# drutest2.net
KiCad netlist of a schematic drawn in EAGLE
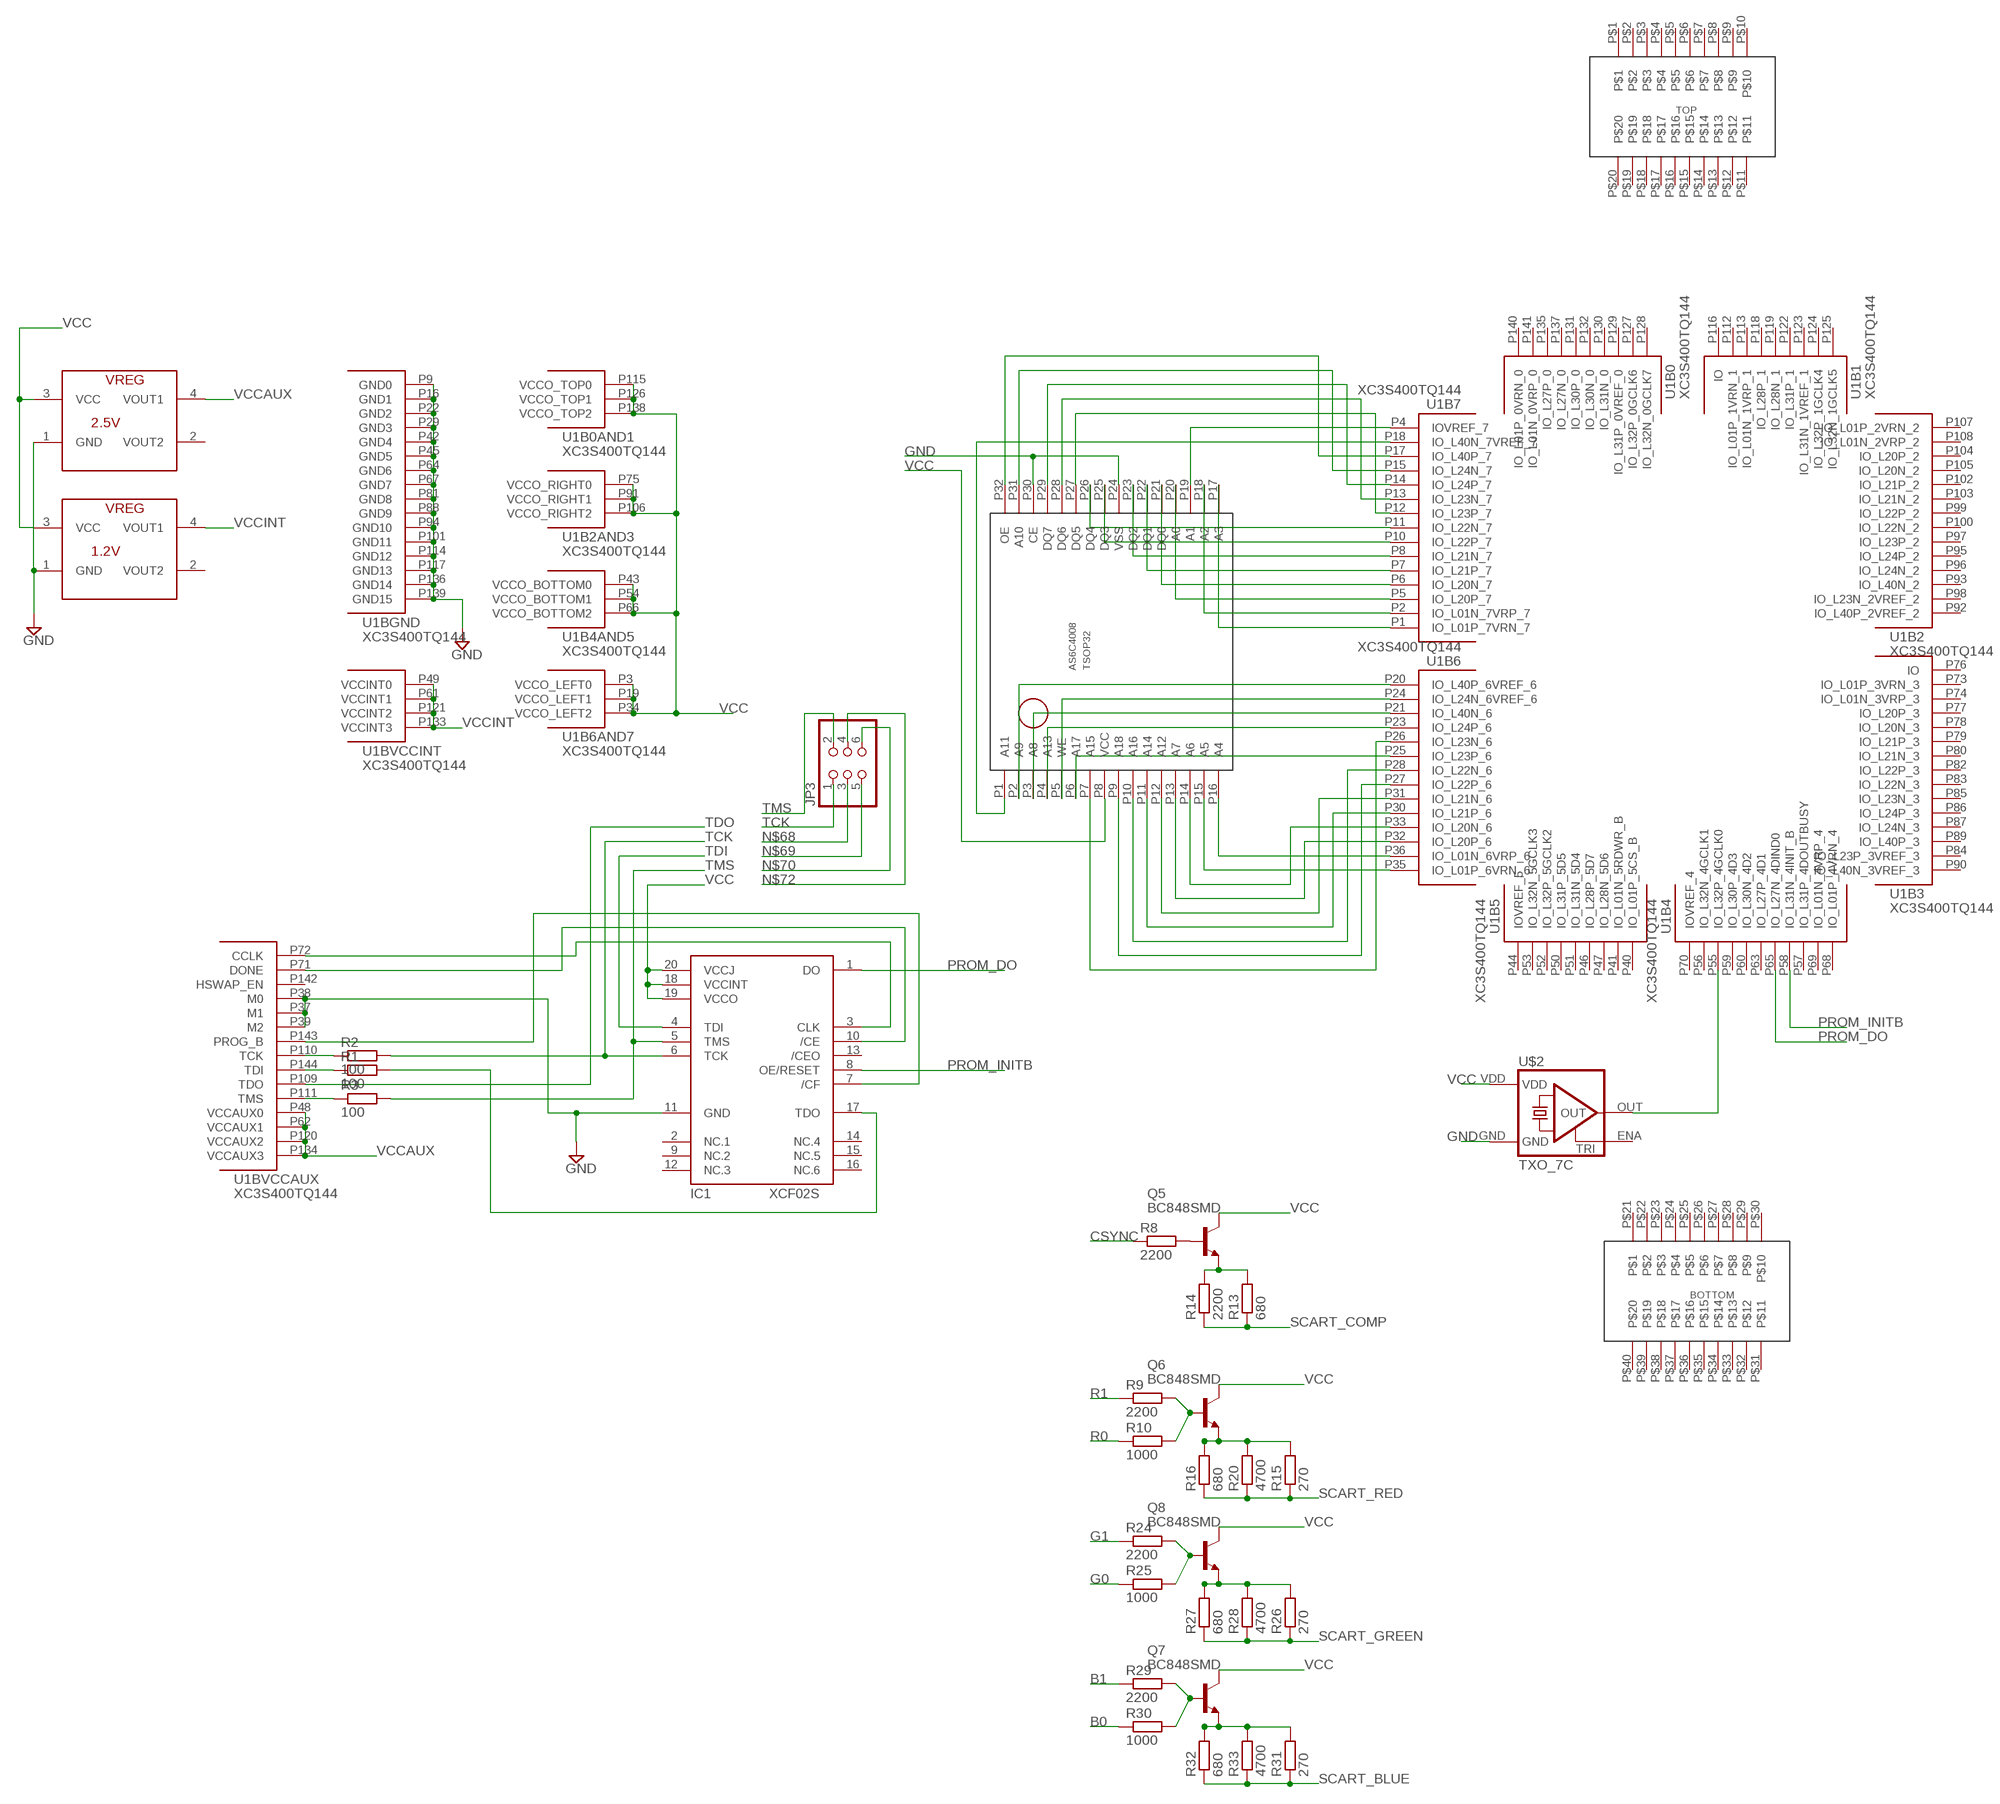
[diagram p0: schematic, sheet 1, part 1 of 2]
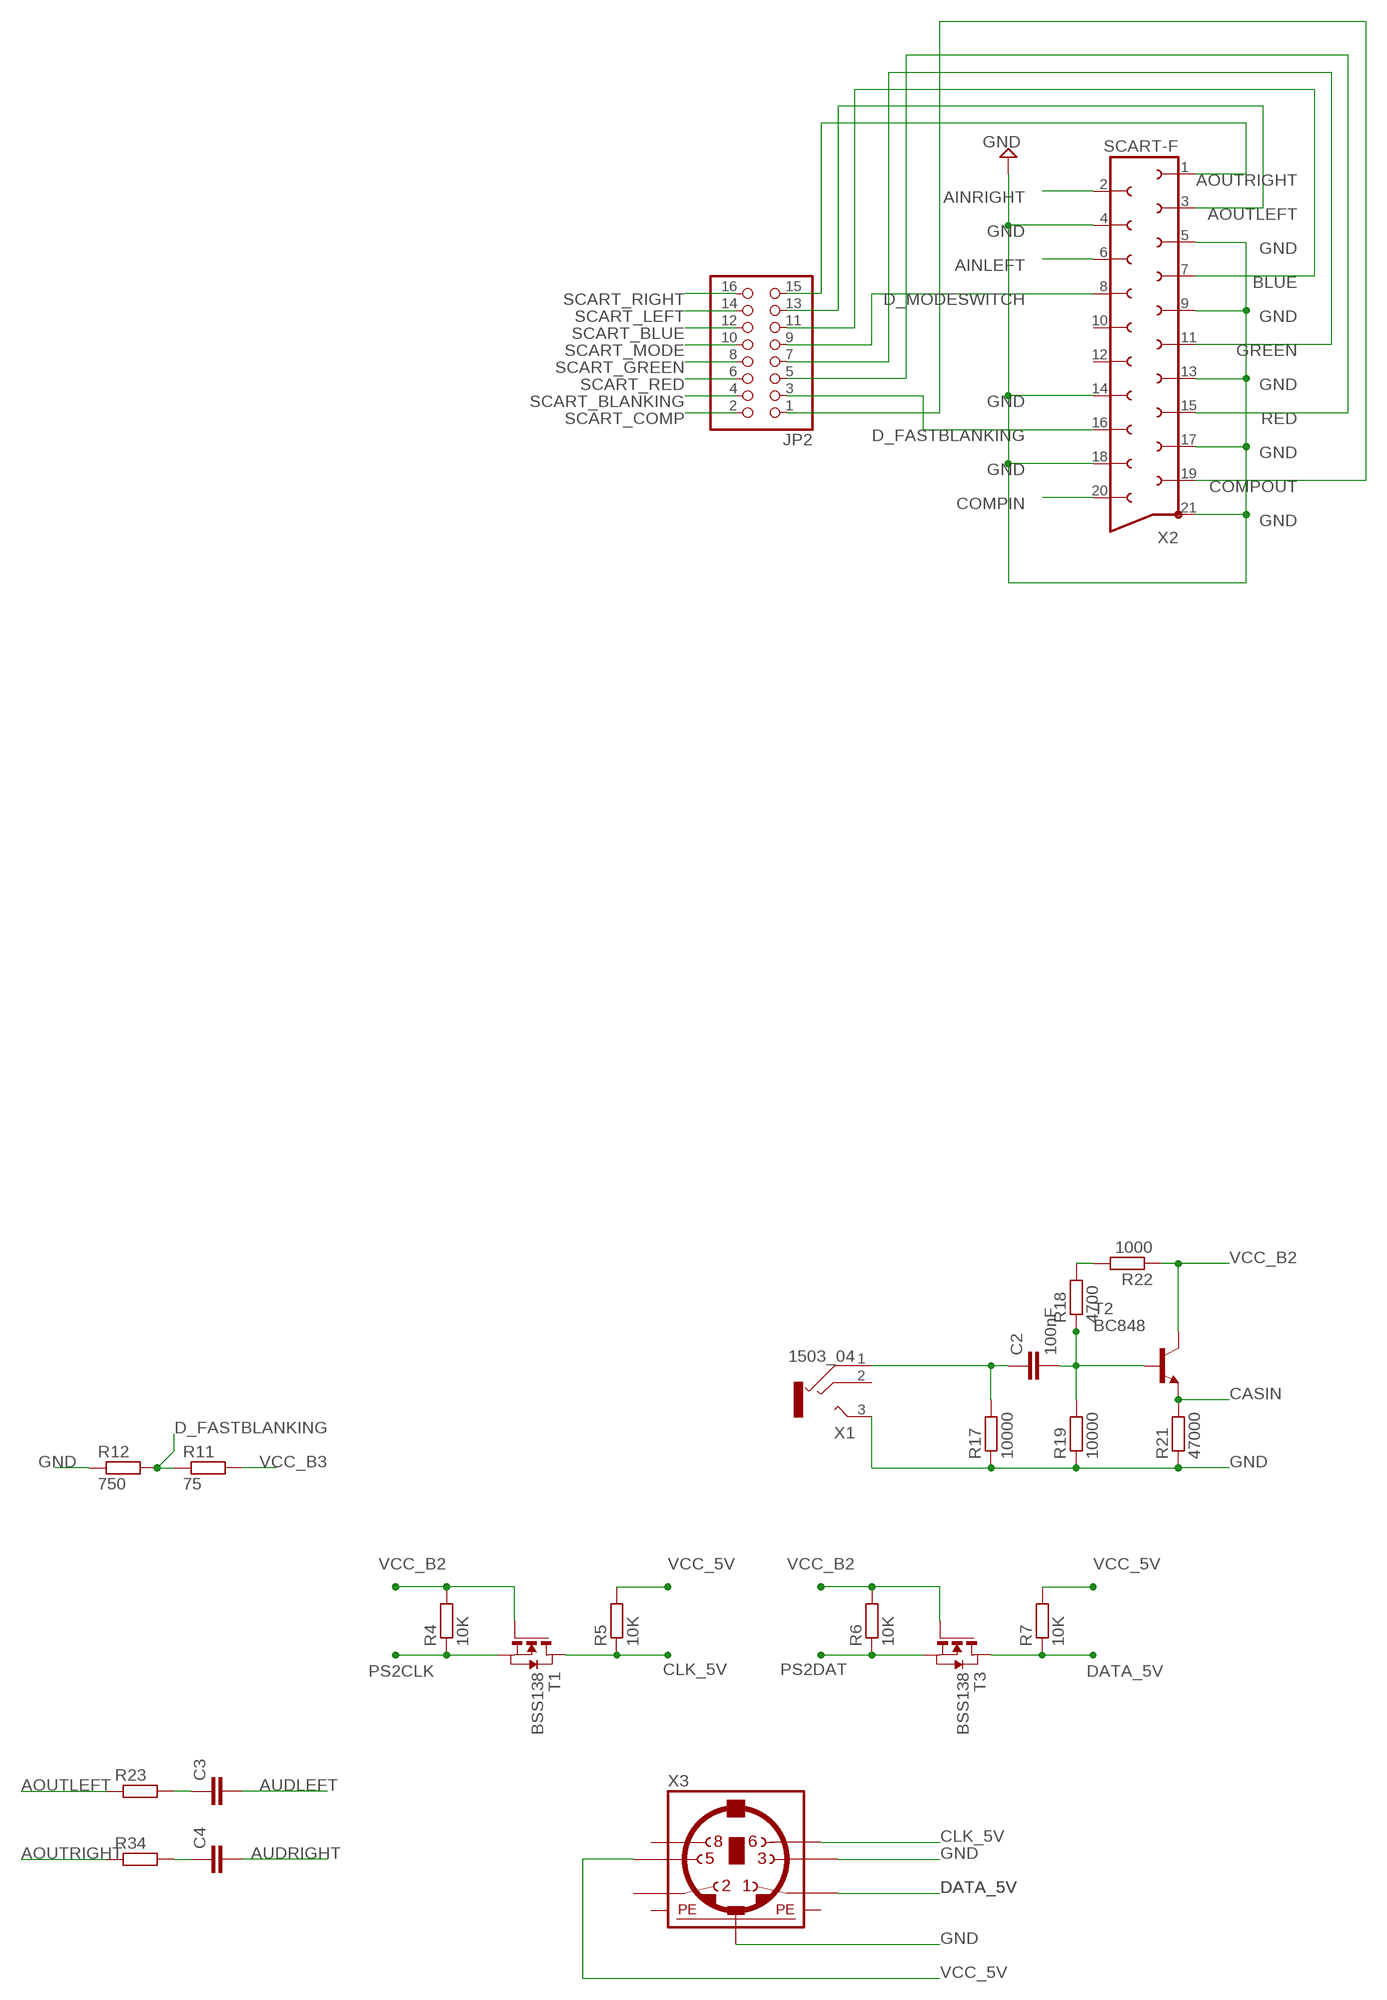
[diagram p1: schematic, sheet 1, part 2 of 2]

(export (version "E")
  (design (tool "Eeschema 10.0.6"))
  (components
    (comp (ref "C2")
      (value "100nF")
      (footprint "eagle-import:C0603")
      (libsource (lib "eagle-import") (part "C-EUC0603"))
    )
    (comp (ref "C3")
      (value "C-EUC0603")
      (footprint "eagle-import:C0603")
      (libsource (lib "eagle-import") (part "C-EUC0603"))
    )
    (comp (ref "C4")
      (value "C-EUC0603")
      (footprint "eagle-import:C0603")
      (libsource (lib "eagle-import") (part "C-EUC0603"))
    )
    (comp (ref "IC1")
      (value "XCF02S")
      (footprint "eagle-import:VO20")
      (libsource (lib "eagle-import") (part "XCF02S"))
    )
    (comp (ref "JP2")
      (value "PINHD-2X8")
      (footprint "eagle-import:2X08")
      (libsource (lib "eagle-import") (part "PINHD-2X8"))
    )
    (comp (ref "JP3")
      (value "PINHD-2X3")
      (footprint "eagle-import:2X03")
      (libsource (lib "eagle-import") (part "PINHD-2X3"))
    )
    (comp (ref "Q5")
      (value "BC848SMD")
      (footprint "eagle-import:SOT23")
      (libsource (lib "eagle-import") (part "BC848SMD"))
    )
    (comp (ref "Q6")
      (value "BC848SMD")
      (footprint "eagle-import:SOT23")
      (libsource (lib "eagle-import") (part "BC848SMD"))
    )
    (comp (ref "Q7")
      (value "BC848SMD")
      (footprint "eagle-import:SOT23")
      (libsource (lib "eagle-import") (part "BC848SMD"))
    )
    (comp (ref "Q8")
      (value "BC848SMD")
      (footprint "eagle-import:SOT23")
      (libsource (lib "eagle-import") (part "BC848SMD"))
    )
    (comp (ref "R1")
      (value "100")
      (footprint "eagle-import:R0805")
      (libsource (lib "eagle-import") (part "R-EU_R0805"))
    )
    (comp (ref "R2")
      (value "100")
      (footprint "eagle-import:R0805")
      (libsource (lib "eagle-import") (part "R-EU_R0805"))
    )
    (comp (ref "R3")
      (value "100")
      (footprint "eagle-import:R0805")
      (libsource (lib "eagle-import") (part "R-EU_R0805"))
    )
    (comp (ref "R4")
      (value "10K")
      (footprint "eagle-import:R0805")
      (libsource (lib "eagle-import") (part "R-EU_R0805"))
    )
    (comp (ref "R5")
      (value "10K")
      (footprint "eagle-import:R0805")
      (libsource (lib "eagle-import") (part "R-EU_R0805"))
    )
    (comp (ref "R6")
      (value "10K")
      (footprint "eagle-import:R0805")
      (libsource (lib "eagle-import") (part "R-EU_R0805"))
    )
    (comp (ref "R7")
      (value "10K")
      (footprint "eagle-import:R0805")
      (libsource (lib "eagle-import") (part "R-EU_R0805"))
    )
    (comp (ref "R8")
      (value "2200")
      (footprint "eagle-import:R0805")
      (libsource (lib "eagle-import") (part "R-EU_R0805"))
    )
    (comp (ref "R9")
      (value "2200")
      (footprint "eagle-import:R0805")
      (libsource (lib "eagle-import") (part "R-EU_R0805"))
    )
    (comp (ref "R10")
      (value "1000")
      (footprint "eagle-import:R0805")
      (libsource (lib "eagle-import") (part "R-EU_R0805"))
    )
    (comp (ref "R11")
      (value "75")
      (footprint "eagle-import:R0805")
      (libsource (lib "eagle-import") (part "R-EU_R0805"))
    )
    (comp (ref "R12")
      (value "750")
      (footprint "eagle-import:R0805")
      (libsource (lib "eagle-import") (part "R-EU_R0805"))
    )
    (comp (ref "R13")
      (value "680")
      (footprint "eagle-import:R0805")
      (libsource (lib "eagle-import") (part "R-EU_R0805"))
    )
    (comp (ref "R14")
      (value "2200")
      (footprint "eagle-import:R0805")
      (libsource (lib "eagle-import") (part "R-EU_R0805"))
    )
    (comp (ref "R15")
      (value "270")
      (footprint "eagle-import:R0805")
      (libsource (lib "eagle-import") (part "R-EU_R0805"))
    )
    (comp (ref "R16")
      (value "680")
      (footprint "eagle-import:R0805")
      (libsource (lib "eagle-import") (part "R-EU_R0805"))
    )
    (comp (ref "R17")
      (value "10000")
      (footprint "eagle-import:R0805")
      (libsource (lib "eagle-import") (part "R-EU_R0805"))
    )
    (comp (ref "R18")
      (value "4700")
      (footprint "eagle-import:R0805")
      (libsource (lib "eagle-import") (part "R-EU_R0805"))
    )
    (comp (ref "R19")
      (value "10000")
      (footprint "eagle-import:R0805")
      (libsource (lib "eagle-import") (part "R-EU_R0805"))
    )
    (comp (ref "R20")
      (value "4700")
      (footprint "eagle-import:R0805")
      (libsource (lib "eagle-import") (part "R-EU_R0805"))
    )
    (comp (ref "R21")
      (value "47000")
      (footprint "eagle-import:R0805")
      (libsource (lib "eagle-import") (part "R-EU_R0805"))
    )
    (comp (ref "R22")
      (value "1000")
      (footprint "eagle-import:R0805")
      (libsource (lib "eagle-import") (part "R-EU_R0805"))
    )
    (comp (ref "R23")
      (value "R-EU_M0805")
      (footprint "eagle-import:M0805")
      (libsource (lib "eagle-import") (part "resistor_R-EU_M0805"))
    )
    (comp (ref "R24")
      (value "2200")
      (footprint "eagle-import:R0805")
      (libsource (lib "eagle-import") (part "R-EU_R0805"))
    )
    (comp (ref "R25")
      (value "1000")
      (footprint "eagle-import:R0805")
      (libsource (lib "eagle-import") (part "R-EU_R0805"))
    )
    (comp (ref "R26")
      (value "270")
      (footprint "eagle-import:R0805")
      (libsource (lib "eagle-import") (part "R-EU_R0805"))
    )
    (comp (ref "R27")
      (value "680")
      (footprint "eagle-import:R0805")
      (libsource (lib "eagle-import") (part "R-EU_R0805"))
    )
    (comp (ref "R28")
      (value "4700")
      (footprint "eagle-import:R0805")
      (libsource (lib "eagle-import") (part "R-EU_R0805"))
    )
    (comp (ref "R29")
      (value "2200")
      (footprint "eagle-import:R0805")
      (libsource (lib "eagle-import") (part "R-EU_R0805"))
    )
    (comp (ref "R30")
      (value "1000")
      (footprint "eagle-import:R0805")
      (libsource (lib "eagle-import") (part "R-EU_R0805"))
    )
    (comp (ref "R31")
      (value "270")
      (footprint "eagle-import:R0805")
      (libsource (lib "eagle-import") (part "R-EU_R0805"))
    )
    (comp (ref "R32")
      (value "680")
      (footprint "eagle-import:R0805")
      (libsource (lib "eagle-import") (part "R-EU_R0805"))
    )
    (comp (ref "R33")
      (value "4700")
      (footprint "eagle-import:R0805")
      (libsource (lib "eagle-import") (part "R-EU_R0805"))
    )
    (comp (ref "R34")
      (value "R-EU_M0805")
      (footprint "eagle-import:M0805")
      (libsource (lib "eagle-import") (part "resistor_R-EU_M0805"))
    )
    (comp (ref "T1")
      (value "BSS138")
      (footprint "eagle-import:SOT-23")
      (libsource (lib "eagle-import") (part "NMOSSOT23"))
    )
    (comp (ref "T2")
      (value "BC848")
      (footprint "eagle-import:SOT23")
      (libsource (lib "eagle-import") (part "BC848"))
    )
    (comp (ref "T3")
      (value "BSS138")
      (footprint "eagle-import:SOT-23")
      (libsource (lib "eagle-import") (part "NMOSSOT23"))
    )
    (comp (ref "U$1")
      (value "AS6C4008")
      (footprint "eagle-import:TSOP32")
      (libsource (lib "eagle-import") (part "AS6C4008"))
    )
    (comp (ref "U$2")
      (value "TXO_7C")
      (footprint "eagle-import:OSC_7C")
      (libsource (lib "eagle-import") (part "TXO_7C"))
    )
    (comp (ref "U$3")
      (value "2.5V")
      (footprint "eagle-import:SOT223")
      (libsource (lib "eagle-import") (part "NX1117"))
    )
    (comp (ref "U$4")
      (value "1.2V")
      (footprint "eagle-import:SOT223")
      (libsource (lib "eagle-import") (part "NX1117"))
    )
    (comp (ref "U$5")
      (value "EXPHDR")
      (footprint "eagle-import:EXPHDR")
      (libsource (lib "eagle-import") (part "EXPHDR"))
    )
    (comp (ref "U1")
      (value "XC3S400TQ144")
      (footprint "eagle-import:TQ144")
      (libsource (lib "eagle-import") (part "XC3S400TQ144"))
    )
    (comp (ref "X1")
      (value "1503_04")
      (footprint "eagle-import:1503_04")
      (libsource (lib "eagle-import") (part "1503_04"))
    )
    (comp (ref "X2")
      (value "SCART-F")
      (footprint "eagle-import:SCART-F")
      (libsource (lib "eagle-import") (part "SCART-F"))
    )
    (comp (ref "X3")
      (value "MINI_DIN_6")
      (footprint "eagle-import:M_DIN6")
      (libsource (lib "eagle-import") (part "MINI_DIN_6"))
    )
  )
  (nets
    (net (code "1") (name "/AINLEFT") (class "Default")
      (node (ref "X2") (pin "6") (pinfunction "6_6") (pintype "passive"))
    )
    (net (code "2") (name "/AINRIGHT") (class "Default")
      (node (ref "X2") (pin "2") (pinfunction "2_2") (pintype "passive"))
    )
    (net (code "3") (name "/AOUTLEFT") (class "Default")
      (node (ref "JP2") (pin "13") (pinfunction "13_13") (pintype "passive"))
      (node (ref "R23") (pin "1") (pinfunction "1_1") (pintype "passive"))
      (node (ref "X2") (pin "3") (pinfunction "3_3") (pintype "passive"))
    )
    (net (code "4") (name "/AOUTRIGHT") (class "Default")
      (node (ref "JP2") (pin "15") (pinfunction "15_15") (pintype "passive"))
      (node (ref "R34") (pin "1") (pinfunction "1_1") (pintype "passive"))
      (node (ref "X2") (pin "1") (pinfunction "1_1") (pintype "passive"))
    )
    (net (code "5") (name "/AUDLEFT") (class "Default")
      (node (ref "C3") (pin "2") (pinfunction "2_2") (pintype "passive"))
    )
    (net (code "6") (name "/AUDRIGHT") (class "Default")
      (node (ref "C4") (pin "2") (pinfunction "2_2") (pintype "passive"))
    )
    (net (code "7") (name "/B0") (class "Default")
      (node (ref "R30") (pin "1") (pinfunction "1_1") (pintype "passive"))
    )
    (net (code "8") (name "/B1") (class "Default")
      (node (ref "R29") (pin "1") (pinfunction "1_1") (pintype "passive"))
    )
    (net (code "9") (name "/BLUE") (class "Default")
      (node (ref "JP2") (pin "11") (pinfunction "11_11") (pintype "passive"))
      (node (ref "X2") (pin "7") (pinfunction "7_7") (pintype "passive"))
    )
    (net (code "10") (name "/CASIN") (class "Default")
      (node (ref "R21") (pin "2") (pinfunction "2_2") (pintype "passive"))
      (node (ref "T2") (pin "2") (pinfunction "E_2") (pintype "passive"))
    )
    (net (code "11") (name "/CLK_5V") (class "Default")
      (node (ref "R5") (pin "1") (pinfunction "1_1") (pintype "passive"))
      (node (ref "T1") (pin "1") (pinfunction "D_1") (pintype "passive"))
      (node (ref "X3") (pin "6") (pinfunction "6_6") (pintype "passive"))
    )
    (net (code "12") (name "/COMPIN") (class "Default")
      (node (ref "X2") (pin "20") (pinfunction "20_20") (pintype "passive"))
    )
    (net (code "13") (name "/COMPOUT") (class "Default")
      (node (ref "JP2") (pin "1") (pinfunction "1_1") (pintype "passive"))
      (node (ref "X2") (pin "19") (pinfunction "19_19") (pintype "passive"))
    )
    (net (code "14") (name "/CSYNC") (class "Default")
      (node (ref "R8") (pin "1") (pinfunction "1_1") (pintype "passive"))
    )
    (net (code "15") (name "/DATA_5V") (class "Default")
      (node (ref "R7") (pin "1") (pinfunction "1_1") (pintype "passive"))
      (node (ref "T3") (pin "1") (pinfunction "D_1") (pintype "passive"))
      (node (ref "X3") (pin "1") (pinfunction "1_1") (pintype "passive"))
    )
    (net (code "16") (name "/D_FASTBLANKING") (class "Default")
      (node (ref "JP2") (pin "3") (pinfunction "3_3") (pintype "passive"))
      (node (ref "R11") (pin "1") (pinfunction "1_1") (pintype "passive"))
      (node (ref "R12") (pin "2") (pinfunction "2_2") (pintype "passive"))
      (node (ref "X2") (pin "16") (pinfunction "16_16") (pintype "passive"))
    )
    (net (code "17") (name "/D_MODESWITCH") (class "Default")
      (node (ref "JP2") (pin "9") (pinfunction "9_9") (pintype "passive"))
      (node (ref "X2") (pin "8") (pinfunction "8_8") (pintype "passive"))
    )
    (net (code "18") (name "/G0") (class "Default")
      (node (ref "R25") (pin "1") (pinfunction "1_1") (pintype "passive"))
    )
    (net (code "19") (name "/G1") (class "Default")
      (node (ref "R24") (pin "1") (pinfunction "1_1") (pintype "passive"))
    )
    (net (code "20") (name "/GREEN") (class "Default")
      (node (ref "JP2") (pin "7") (pinfunction "7_7") (pintype "passive"))
      (node (ref "X2") (pin "11") (pinfunction "11_11") (pintype "passive"))
    )
    (net (code "21") (name "/N$68") (class "Default")
      (node (ref "JP3") (pin "3") (pinfunction "3_3") (pintype "passive"))
    )
    (net (code "22") (name "/N$69") (class "Default")
      (node (ref "JP3") (pin "5") (pinfunction "5_5") (pintype "passive"))
    )
    (net (code "23") (name "/N$70") (class "Default")
      (node (ref "JP3") (pin "6") (pinfunction "6_6") (pintype "passive"))
    )
    (net (code "24") (name "/N$72") (class "Default")
      (node (ref "JP3") (pin "4") (pinfunction "4_4") (pintype "passive"))
    )
    (net (code "25") (name "/PE1") (class "Default")
      (node (ref "X3") (pin "SH1") (pinfunction "PE1_SH1") (pintype "power_in"))
    )
    (net (code "26") (name "/PE3") (class "Default")
      (node (ref "X3") (pin "SH3") (pinfunction "PE3_SH3") (pintype "power_in"))
    )
    (net (code "27") (name "/PROM_DO") (class "Default")
      (node (ref "IC1") (pin "1") (pinfunction "DO_1") (pintype "bidirectional"))
      (node (ref "U1") (pin "P65") (pinfunction "IO_L27N_4DIND0_P65") (pintype "bidirectional"))
    )
    (net (code "28") (name "/PROM_INITB") (class "Default")
      (node (ref "IC1") (pin "8") (pinfunction "OE/RESET_8") (pintype "bidirectional"))
      (node (ref "U1") (pin "P58") (pinfunction "IO_L31N_4INIT_B_P58") (pintype "bidirectional"))
    )
    (net (code "29") (name "/PS2CLK") (class "Default")
      (node (ref "R4") (pin "1") (pinfunction "1_1") (pintype "passive"))
      (node (ref "T1") (pin "2") (pinfunction "S_2") (pintype "passive"))
    )
    (net (code "30") (name "/PS2DAT") (class "Default")
      (node (ref "R6") (pin "1") (pinfunction "1_1") (pintype "passive"))
      (node (ref "T3") (pin "2") (pinfunction "S_2") (pintype "passive"))
    )
    (net (code "31") (name "/R0") (class "Default")
      (node (ref "R10") (pin "1") (pinfunction "1_1") (pintype "passive"))
    )
    (net (code "32") (name "/R1") (class "Default")
      (node (ref "R9") (pin "1") (pinfunction "1_1") (pintype "passive"))
    )
    (net (code "33") (name "/RED") (class "Default")
      (node (ref "JP2") (pin "5") (pinfunction "5_5") (pintype "passive"))
      (node (ref "X2") (pin "15") (pinfunction "15_15") (pintype "passive"))
    )
    (net (code "34") (name "/SCART_BLANKING") (class "Default")
      (node (ref "JP2") (pin "4") (pinfunction "4_4") (pintype "passive"))
    )
    (net (code "35") (name "/SCART_BLUE") (class "Default")
      (node (ref "JP2") (pin "12") (pinfunction "12_12") (pintype "passive"))
      (node (ref "R31") (pin "1") (pinfunction "1_1") (pintype "passive"))
      (node (ref "R32") (pin "1") (pinfunction "1_1") (pintype "passive"))
      (node (ref "R33") (pin "1") (pinfunction "1_1") (pintype "passive"))
    )
    (net (code "36") (name "/SCART_COMP") (class "Default")
      (node (ref "JP2") (pin "2") (pinfunction "2_2") (pintype "passive"))
      (node (ref "R13") (pin "1") (pinfunction "1_1") (pintype "passive"))
      (node (ref "R14") (pin "1") (pinfunction "1_1") (pintype "passive"))
    )
    (net (code "37") (name "/SCART_GREEN") (class "Default")
      (node (ref "JP2") (pin "8") (pinfunction "8_8") (pintype "passive"))
      (node (ref "R26") (pin "1") (pinfunction "1_1") (pintype "passive"))
      (node (ref "R27") (pin "1") (pinfunction "1_1") (pintype "passive"))
      (node (ref "R28") (pin "1") (pinfunction "1_1") (pintype "passive"))
    )
    (net (code "38") (name "/SCART_LEFT") (class "Default")
      (node (ref "JP2") (pin "14") (pinfunction "14_14") (pintype "passive"))
    )
    (net (code "39") (name "/SCART_MODE") (class "Default")
      (node (ref "JP2") (pin "10") (pinfunction "10_10") (pintype "passive"))
    )
    (net (code "40") (name "/SCART_RED") (class "Default")
      (node (ref "JP2") (pin "6") (pinfunction "6_6") (pintype "passive"))
      (node (ref "R15") (pin "1") (pinfunction "1_1") (pintype "passive"))
      (node (ref "R16") (pin "1") (pinfunction "1_1") (pintype "passive"))
      (node (ref "R20") (pin "1") (pinfunction "1_1") (pintype "passive"))
    )
    (net (code "41") (name "/SCART_RIGHT") (class "Default")
      (node (ref "JP2") (pin "16") (pinfunction "16_16") (pintype "passive"))
    )
    (net (code "42") (name "/TCK") (class "Default")
      (node (ref "IC1") (pin "6") (pinfunction "TCK_6") (pintype "bidirectional"))
      (node (ref "JP3") (pin "1") (pinfunction "1_1") (pintype "passive"))
      (node (ref "R2") (pin "2") (pinfunction "2_2") (pintype "passive"))
    )
    (net (code "43") (name "/TDI") (class "Default")
      (node (ref "IC1") (pin "4") (pinfunction "TDI_4") (pintype "bidirectional"))
    )
    (net (code "44") (name "/TDO") (class "Default")
      (node (ref "U1") (pin "P109") (pinfunction "TDO_P109") (pintype "bidirectional"))
    )
    (net (code "45") (name "/TMS") (class "Default")
      (node (ref "IC1") (pin "5") (pinfunction "TMS_5") (pintype "bidirectional"))
      (node (ref "JP3") (pin "2") (pinfunction "2_2") (pintype "passive"))
      (node (ref "R3") (pin "2") (pinfunction "2_2") (pintype "passive"))
    )
    (net (code "46") (name "/VCC") (class "Default")
      (node (ref "IC1") (pin "18") (pinfunction "VCCINT_18") (pintype "bidirectional"))
      (node (ref "IC1") (pin "19") (pinfunction "VCCO_19") (pintype "bidirectional"))
      (node (ref "IC1") (pin "20") (pinfunction "VCCJ_20") (pintype "bidirectional"))
      (node (ref "Q5") (pin "3") (pinfunction "C_3") (pintype "passive"))
      (node (ref "Q6") (pin "3") (pinfunction "C_3") (pintype "passive"))
      (node (ref "Q7") (pin "3") (pinfunction "C_3") (pintype "passive"))
      (node (ref "Q8") (pin "3") (pinfunction "C_3") (pintype "passive"))
      (node (ref "U$1") (pin "P8") (pinfunction "VCC_P8") (pintype "bidirectional"))
      (node (ref "U$2") (pin "VDD") (pinfunction "VDD_VDD") (pintype "power_in"))
      (node (ref "U$3") (pin "3") (pinfunction "VCC_3") (pintype "bidirectional"))
      (node (ref "U$4") (pin "3") (pinfunction "VCC_3") (pintype "bidirectional"))
      (node (ref "U1") (pin "P106") (pinfunction "VCCO_RIGHT2_P106") (pintype "passive"))
      (node (ref "U1") (pin "P115") (pinfunction "VCCO_TOP0_P115") (pintype "passive"))
      (node (ref "U1") (pin "P126") (pinfunction "VCCO_TOP1_P126") (pintype "passive"))
      (node (ref "U1") (pin "P138") (pinfunction "VCCO_TOP2_P138") (pintype "passive"))
      (node (ref "U1") (pin "P19") (pinfunction "VCCO_LEFT1_P19") (pintype "passive"))
      (node (ref "U1") (pin "P3") (pinfunction "VCCO_LEFT0_P3") (pintype "passive"))
      (node (ref "U1") (pin "P34") (pinfunction "VCCO_LEFT2_P34") (pintype "passive"))
      (node (ref "U1") (pin "P43") (pinfunction "VCCO_BOTTOM0_P43") (pintype "passive"))
      (node (ref "U1") (pin "P54") (pinfunction "VCCO_BOTTOM1_P54") (pintype "passive"))
      (node (ref "U1") (pin "P66") (pinfunction "VCCO_BOTTOM2_P66") (pintype "passive"))
      (node (ref "U1") (pin "P75") (pinfunction "VCCO_RIGHT0_P75") (pintype "passive"))
      (node (ref "U1") (pin "P91") (pinfunction "VCCO_RIGHT1_P91") (pintype "passive"))
    )
    (net (code "47") (name "/VCCAUX") (class "Default")
      (node (ref "U$3") (pin "4") (pinfunction "VOUT1_4") (pintype "bidirectional"))
      (node (ref "U1") (pin "P120") (pinfunction "VCCAUX2_P120") (pintype "passive"))
      (node (ref "U1") (pin "P134") (pinfunction "VCCAUX3_P134") (pintype "passive"))
      (node (ref "U1") (pin "P48") (pinfunction "VCCAUX0_P48") (pintype "passive"))
      (node (ref "U1") (pin "P62") (pinfunction "VCCAUX1_P62") (pintype "passive"))
    )
    (net (code "48") (name "/VCCINT") (class "Default")
      (node (ref "U$4") (pin "4") (pinfunction "VOUT1_4") (pintype "bidirectional"))
      (node (ref "U1") (pin "P121") (pinfunction "VCCINT2_P121") (pintype "passive"))
      (node (ref "U1") (pin "P133") (pinfunction "VCCINT3_P133") (pintype "passive"))
      (node (ref "U1") (pin "P49") (pinfunction "VCCINT0_P49") (pintype "passive"))
      (node (ref "U1") (pin "P61") (pinfunction "VCCINT1_P61") (pintype "passive"))
    )
    (net (code "49") (name "/VCC_5V") (class "Default")
      (node (ref "R5") (pin "2") (pinfunction "2_2") (pintype "passive"))
      (node (ref "R7") (pin "2") (pinfunction "2_2") (pintype "passive"))
      (node (ref "X3") (pin "5") (pinfunction "5_5") (pintype "passive"))
    )
    (net (code "50") (name "/VCC_B2") (class "Default")
      (node (ref "R22") (pin "1") (pinfunction "1_1") (pintype "passive"))
      (node (ref "R4") (pin "2") (pinfunction "2_2") (pintype "passive"))
      (node (ref "R6") (pin "2") (pinfunction "2_2") (pintype "passive"))
      (node (ref "T1") (pin "3") (pinfunction "G_3") (pintype "passive"))
      (node (ref "T2") (pin "3") (pinfunction "C_3") (pintype "passive"))
      (node (ref "T3") (pin "3") (pinfunction "G_3") (pintype "passive"))
    )
    (net (code "51") (name "/VCC_B3") (class "Default")
      (node (ref "R11") (pin "2") (pinfunction "2_2") (pintype "passive"))
    )
    (net (code "52") (name "GND") (class "Default")
      (node (ref "IC1") (pin "11") (pinfunction "GND_11") (pintype "bidirectional"))
      (node (ref "R12") (pin "1") (pinfunction "1_1") (pintype "passive"))
      (node (ref "R17") (pin "1") (pinfunction "1_1") (pintype "passive"))
      (node (ref "R19") (pin "1") (pinfunction "1_1") (pintype "passive"))
      (node (ref "R21") (pin "1") (pinfunction "1_1") (pintype "passive"))
      (node (ref "U$1") (pin "P24") (pinfunction "VSS_P24") (pintype "bidirectional"))
      (node (ref "U$1") (pin "P30") (pinfunction "CE_P30") (pintype "bidirectional"))
      (node (ref "U$2") (pin "GND") (pinfunction "GND_GND") (pintype "power_in"))
      (node (ref "U$3") (pin "1") (pinfunction "GND_1") (pintype "bidirectional"))
      (node (ref "U$4") (pin "1") (pinfunction "GND_1") (pintype "bidirectional"))
      (node (ref "U1") (pin "P101") (pinfunction "GND11_P101") (pintype "passive"))
      (node (ref "U1") (pin "P114") (pinfunction "GND12_P114") (pintype "passive"))
      (node (ref "U1") (pin "P117") (pinfunction "GND13_P117") (pintype "passive"))
      (node (ref "U1") (pin "P136") (pinfunction "GND14_P136") (pintype "passive"))
      (node (ref "U1") (pin "P139") (pinfunction "GND15_P139") (pintype "passive"))
      (node (ref "U1") (pin "P16") (pinfunction "GND1_P16") (pintype "passive"))
      (node (ref "U1") (pin "P22") (pinfunction "GND2_P22") (pintype "passive"))
      (node (ref "U1") (pin "P29") (pinfunction "GND3_P29") (pintype "passive"))
      (node (ref "U1") (pin "P37") (pinfunction "M1_P37") (pintype "bidirectional"))
      (node (ref "U1") (pin "P38") (pinfunction "M0_P38") (pintype "bidirectional"))
      (node (ref "U1") (pin "P39") (pinfunction "M2_P39") (pintype "bidirectional"))
      (node (ref "U1") (pin "P42") (pinfunction "GND4_P42") (pintype "passive"))
      (node (ref "U1") (pin "P45") (pinfunction "GND5_P45") (pintype "passive"))
      (node (ref "U1") (pin "P64") (pinfunction "GND6_P64") (pintype "passive"))
      (node (ref "U1") (pin "P67") (pinfunction "GND7_P67") (pintype "passive"))
      (node (ref "U1") (pin "P81") (pinfunction "GND8_P81") (pintype "passive"))
      (node (ref "U1") (pin "P88") (pinfunction "GND9_P88") (pintype "passive"))
      (node (ref "U1") (pin "P9") (pinfunction "GND0_P9") (pintype "passive"))
      (node (ref "U1") (pin "P94") (pinfunction "GND10_P94") (pintype "passive"))
      (node (ref "X1") (pin "3") (pinfunction "2_3") (pintype "passive"))
      (node (ref "X2") (pin "13") (pinfunction "13_13") (pintype "passive"))
      (node (ref "X2") (pin "14") (pinfunction "14_14") (pintype "passive"))
      (node (ref "X2") (pin "17") (pinfunction "17_17") (pintype "passive"))
      (node (ref "X2") (pin "18") (pinfunction "18_18") (pintype "passive"))
      (node (ref "X2") (pin "21") (pinfunction "21_21") (pintype "passive"))
      (node (ref "X2") (pin "4") (pinfunction "4_4") (pintype "passive"))
      (node (ref "X2") (pin "5") (pinfunction "5_5") (pintype "passive"))
      (node (ref "X2") (pin "9") (pinfunction "9_9") (pintype "passive"))
      (node (ref "X3") (pin "3") (pinfunction "3_3") (pintype "passive"))
      (node (ref "X3") (pin "SH2") (pinfunction "PE2_SH2") (pintype "power_in"))
    )
    (net (code "53") (name "Net-(C2-Pad1)") (class "Default")
      (node (ref "C2") (pin "1") (pinfunction "1_1") (pintype "passive"))
      (node (ref "R17") (pin "2") (pinfunction "2_2") (pintype "passive"))
      (node (ref "X1") (pin "1") (pinfunction "1_1") (pintype "passive"))
    )
    (net (code "54") (name "Net-(C3-Pad1)") (class "Default")
      (node (ref "C3") (pin "1") (pinfunction "1_1") (pintype "passive"))
      (node (ref "R23") (pin "2") (pinfunction "2_2") (pintype "passive"))
    )
    (net (code "55") (name "Net-(C4-Pad1)") (class "Default")
      (node (ref "C4") (pin "1") (pinfunction "1_1") (pintype "passive"))
      (node (ref "R34") (pin "2") (pinfunction "2_2") (pintype "passive"))
    )
    (net (code "56") (name "Net-(IC1-CLK)") (class "Default")
      (node (ref "IC1") (pin "3") (pinfunction "CLK_3") (pintype "bidirectional"))
      (node (ref "U1") (pin "P72") (pinfunction "CCLK_P72") (pintype "bidirectional"))
    )
    (net (code "57") (name "Net-(IC1-TDO)") (class "Default")
      (node (ref "IC1") (pin "17") (pinfunction "TDO_17") (pintype "bidirectional"))
      (node (ref "R1") (pin "2") (pinfunction "2_2") (pintype "passive"))
    )
    (net (code "58") (name "Net-(IC1-{slash}CE)") (class "Default")
      (node (ref "IC1") (pin "10") (pinfunction "/CE_10") (pintype "bidirectional"))
      (node (ref "U1") (pin "P71") (pinfunction "DONE_P71") (pintype "bidirectional"))
    )
    (net (code "59") (name "Net-(IC1-{slash}CF)") (class "Default")
      (node (ref "IC1") (pin "7") (pinfunction "/CF_7") (pintype "bidirectional"))
      (node (ref "U1") (pin "P143") (pinfunction "PROG_B_P143") (pintype "bidirectional"))
    )
    (net (code "60") (name "Net-(Q5-B)") (class "Default")
      (node (ref "Q5") (pin "1") (pinfunction "B_1") (pintype "passive"))
      (node (ref "R8") (pin "2") (pinfunction "2_2") (pintype "passive"))
    )
    (net (code "61") (name "Net-(Q5-E)") (class "Default")
      (node (ref "Q5") (pin "2") (pinfunction "E_2") (pintype "passive"))
      (node (ref "R13") (pin "2") (pinfunction "2_2") (pintype "passive"))
      (node (ref "R14") (pin "2") (pinfunction "2_2") (pintype "passive"))
    )
    (net (code "62") (name "Net-(Q6-B)") (class "Default")
      (node (ref "Q6") (pin "1") (pinfunction "B_1") (pintype "passive"))
      (node (ref "R10") (pin "2") (pinfunction "2_2") (pintype "passive"))
      (node (ref "R9") (pin "2") (pinfunction "2_2") (pintype "passive"))
    )
    (net (code "63") (name "Net-(Q6-E)") (class "Default")
      (node (ref "Q6") (pin "2") (pinfunction "E_2") (pintype "passive"))
      (node (ref "R15") (pin "2") (pinfunction "2_2") (pintype "passive"))
      (node (ref "R16") (pin "2") (pinfunction "2_2") (pintype "passive"))
      (node (ref "R20") (pin "2") (pinfunction "2_2") (pintype "passive"))
    )
    (net (code "64") (name "Net-(Q7-B)") (class "Default")
      (node (ref "Q7") (pin "1") (pinfunction "B_1") (pintype "passive"))
      (node (ref "R29") (pin "2") (pinfunction "2_2") (pintype "passive"))
      (node (ref "R30") (pin "2") (pinfunction "2_2") (pintype "passive"))
    )
    (net (code "65") (name "Net-(Q7-E)") (class "Default")
      (node (ref "Q7") (pin "2") (pinfunction "E_2") (pintype "passive"))
      (node (ref "R31") (pin "2") (pinfunction "2_2") (pintype "passive"))
      (node (ref "R32") (pin "2") (pinfunction "2_2") (pintype "passive"))
      (node (ref "R33") (pin "2") (pinfunction "2_2") (pintype "passive"))
    )
    (net (code "66") (name "Net-(Q8-B)") (class "Default")
      (node (ref "Q8") (pin "1") (pinfunction "B_1") (pintype "passive"))
      (node (ref "R24") (pin "2") (pinfunction "2_2") (pintype "passive"))
      (node (ref "R25") (pin "2") (pinfunction "2_2") (pintype "passive"))
    )
    (net (code "67") (name "Net-(Q8-E)") (class "Default")
      (node (ref "Q8") (pin "2") (pinfunction "E_2") (pintype "passive"))
      (node (ref "R26") (pin "2") (pinfunction "2_2") (pintype "passive"))
      (node (ref "R27") (pin "2") (pinfunction "2_2") (pintype "passive"))
      (node (ref "R28") (pin "2") (pinfunction "2_2") (pintype "passive"))
    )
    (net (code "68") (name "Net-(R18-Pad2)") (class "Default")
      (node (ref "R18") (pin "2") (pinfunction "2_2") (pintype "passive"))
      (node (ref "R22") (pin "2") (pinfunction "2_2") (pintype "passive"))
    )
    (net (code "69") (name "Net-(T2-B)") (class "Default")
      (node (ref "C2") (pin "2") (pinfunction "2_2") (pintype "passive"))
      (node (ref "R18") (pin "1") (pinfunction "1_1") (pintype "passive"))
      (node (ref "R19") (pin "2") (pinfunction "2_2") (pintype "passive"))
      (node (ref "T2") (pin "1") (pinfunction "B_1") (pintype "passive"))
    )
    (net (code "70") (name "Net-(U$1-A0)") (class "Default")
      (node (ref "U$1") (pin "P20") (pinfunction "A0_P20") (pintype "bidirectional"))
      (node (ref "U1") (pin "P5") (pinfunction "IO_L20P_7_P5") (pintype "bidirectional"))
    )
    (net (code "71") (name "Net-(U$1-A1)") (class "Default")
      (node (ref "U$1") (pin "P19") (pinfunction "A1_P19") (pintype "bidirectional"))
      (node (ref "U1") (pin "P4") (pinfunction "IOVREF_7_P4") (pintype "bidirectional"))
    )
    (net (code "72") (name "Net-(U$1-A2)") (class "Default")
      (node (ref "U$1") (pin "P18") (pinfunction "A2_P18") (pintype "bidirectional"))
      (node (ref "U1") (pin "P2") (pinfunction "IO_L01N_7VRP_7_P2") (pintype "bidirectional"))
    )
    (net (code "73") (name "Net-(U$1-A3)") (class "Default")
      (node (ref "U$1") (pin "P17") (pinfunction "A3_P17") (pintype "bidirectional"))
      (node (ref "U1") (pin "P1") (pinfunction "IO_L01P_7VRN_7_P1") (pintype "bidirectional"))
    )
    (net (code "74") (name "Net-(U$1-A4)") (class "Default")
      (node (ref "U$1") (pin "P16") (pinfunction "A4_P16") (pintype "bidirectional"))
      (node (ref "U1") (pin "P36") (pinfunction "IO_L01N_6VRP_6_P36") (pintype "bidirectional"))
    )
    (net (code "75") (name "Net-(U$1-A5)") (class "Default")
      (node (ref "U$1") (pin "P15") (pinfunction "A5_P15") (pintype "bidirectional"))
      (node (ref "U1") (pin "P35") (pinfunction "IO_L01P_6VRN_6_P35") (pintype "bidirectional"))
    )
    (net (code "76") (name "Net-(U$1-A6)") (class "Default")
      (node (ref "U$1") (pin "P14") (pinfunction "A6_P14") (pintype "bidirectional"))
      (node (ref "U1") (pin "P33") (pinfunction "IO_L20N_6_P33") (pintype "bidirectional"))
    )
    (net (code "77") (name "Net-(U$1-A7)") (class "Default")
      (node (ref "U$1") (pin "P13") (pinfunction "A7_P13") (pintype "bidirectional"))
      (node (ref "U1") (pin "P32") (pinfunction "IO_L20P_6_P32") (pintype "bidirectional"))
    )
    (net (code "78") (name "Net-(U$1-A8)") (class "Default")
      (node (ref "U$1") (pin "P3") (pinfunction "A8_P3") (pintype "bidirectional"))
      (node (ref "U1") (pin "P21") (pinfunction "IO_L40N_6_P21") (pintype "bidirectional"))
    )
    (net (code "79") (name "Net-(U$1-A9)") (class "Default")
      (node (ref "U$1") (pin "P2") (pinfunction "A9_P2") (pintype "bidirectional"))
      (node (ref "U1") (pin "P20") (pinfunction "IO_L40P_6VREF_6_P20") (pintype "bidirectional"))
    )
    (net (code "80") (name "Net-(U$1-A10)") (class "Default")
      (node (ref "U$1") (pin "P31") (pinfunction "A10_P31") (pintype "bidirectional"))
      (node (ref "U1") (pin "P15") (pinfunction "IO_L24N_7_P15") (pintype "bidirectional"))
    )
    (net (code "81") (name "Net-(U$1-A11)") (class "Default")
      (node (ref "U$1") (pin "P1") (pinfunction "A11_P1") (pintype "bidirectional"))
      (node (ref "U1") (pin "P18") (pinfunction "IO_L40N_7VREF_7_P18") (pintype "bidirectional"))
    )
    (net (code "82") (name "Net-(U$1-A12)") (class "Default")
      (node (ref "U$1") (pin "P12") (pinfunction "A12_P12") (pintype "bidirectional"))
      (node (ref "U1") (pin "P31") (pinfunction "IO_L21N_6_P31") (pintype "bidirectional"))
    )
    (net (code "83") (name "Net-(U$1-A13)") (class "Default")
      (node (ref "U$1") (pin "P4") (pinfunction "A13_P4") (pintype "bidirectional"))
      (node (ref "U1") (pin "P23") (pinfunction "IO_L24P_6_P23") (pintype "bidirectional"))
    )
    (net (code "84") (name "Net-(U$1-A14)") (class "Default")
      (node (ref "U$1") (pin "P11") (pinfunction "A14_P11") (pintype "bidirectional"))
      (node (ref "U1") (pin "P30") (pinfunction "IO_L21P_6_P30") (pintype "bidirectional"))
    )
    (net (code "85") (name "Net-(U$1-A15)") (class "Default")
      (node (ref "U$1") (pin "P7") (pinfunction "A15_P7") (pintype "bidirectional"))
      (node (ref "U1") (pin "P26") (pinfunction "IO_L23N_6_P26") (pintype "bidirectional"))
    )
    (net (code "86") (name "Net-(U$1-A16)") (class "Default")
      (node (ref "U$1") (pin "P10") (pinfunction "A16_P10") (pintype "bidirectional"))
      (node (ref "U1") (pin "P28") (pinfunction "IO_L22N_6_P28") (pintype "bidirectional"))
    )
    (net (code "87") (name "Net-(U$1-A17)") (class "Default")
      (node (ref "U$1") (pin "P6") (pinfunction "A17_P6") (pintype "bidirectional"))
      (node (ref "U1") (pin "P25") (pinfunction "IO_L23P_6_P25") (pintype "bidirectional"))
    )
    (net (code "88") (name "Net-(U$1-A18)") (class "Default")
      (node (ref "U$1") (pin "P9") (pinfunction "A18_P9") (pintype "bidirectional"))
      (node (ref "U1") (pin "P27") (pinfunction "IO_L22P_6_P27") (pintype "bidirectional"))
    )
    (net (code "89") (name "Net-(U$1-DQ0)") (class "Default")
      (node (ref "U$1") (pin "P21") (pinfunction "DQ0_P21") (pintype "bidirectional"))
      (node (ref "U1") (pin "P6") (pinfunction "IO_L20N_7_P6") (pintype "bidirectional"))
    )
    (net (code "90") (name "Net-(U$1-DQ1)") (class "Default")
      (node (ref "U$1") (pin "P22") (pinfunction "DQ1_P22") (pintype "bidirectional"))
      (node (ref "U1") (pin "P7") (pinfunction "IO_L21P_7_P7") (pintype "bidirectional"))
    )
    (net (code "91") (name "Net-(U$1-DQ2)") (class "Default")
      (node (ref "U$1") (pin "P23") (pinfunction "DQ2_P23") (pintype "bidirectional"))
      (node (ref "U1") (pin "P8") (pinfunction "IO_L21N_7_P8") (pintype "bidirectional"))
    )
    (net (code "92") (name "Net-(U$1-DQ3)") (class "Default")
      (node (ref "U$1") (pin "P25") (pinfunction "DQ3_P25") (pintype "bidirectional"))
      (node (ref "U1") (pin "P10") (pinfunction "IO_L22P_7_P10") (pintype "bidirectional"))
    )
    (net (code "93") (name "Net-(U$1-DQ4)") (class "Default")
      (node (ref "U$1") (pin "P26") (pinfunction "DQ4_P26") (pintype "bidirectional"))
      (node (ref "U1") (pin "P11") (pinfunction "IO_L22N_7_P11") (pintype "bidirectional"))
    )
    (net (code "94") (name "Net-(U$1-DQ5)") (class "Default")
      (node (ref "U$1") (pin "P27") (pinfunction "DQ5_P27") (pintype "bidirectional"))
      (node (ref "U1") (pin "P12") (pinfunction "IO_L23P_7_P12") (pintype "bidirectional"))
    )
    (net (code "95") (name "Net-(U$1-DQ6)") (class "Default")
      (node (ref "U$1") (pin "P28") (pinfunction "DQ6_P28") (pintype "bidirectional"))
      (node (ref "U1") (pin "P13") (pinfunction "IO_L23N_7_P13") (pintype "bidirectional"))
    )
    (net (code "96") (name "Net-(U$1-DQ7)") (class "Default")
      (node (ref "U$1") (pin "P29") (pinfunction "DQ7_P29") (pintype "bidirectional"))
      (node (ref "U1") (pin "P14") (pinfunction "IO_L24P_7_P14") (pintype "bidirectional"))
    )
    (net (code "97") (name "Net-(U$1-OE)") (class "Default")
      (node (ref "U$1") (pin "P32") (pinfunction "OE_P32") (pintype "bidirectional"))
      (node (ref "U1") (pin "P17") (pinfunction "IO_L40P_7_P17") (pintype "bidirectional"))
    )
    (net (code "98") (name "Net-(U$1-WE)") (class "Default")
      (node (ref "U$1") (pin "P5") (pinfunction "WE_P5") (pintype "bidirectional"))
      (node (ref "U1") (pin "P24") (pinfunction "IO_L24N_6VREF_6_P24") (pintype "bidirectional"))
    )
    (net (code "99") (name "Net-(U1G-IO_L32P_4GCLK0)") (class "Default")
      (node (ref "U$2") (pin "OUT") (pinfunction "OUT_OUT") (pintype "output"))
      (node (ref "U1") (pin "P55") (pinfunction "IO_L32P_4GCLK0_P55") (pintype "bidirectional"))
    )
    (net (code "100") (name "Net-(U1N-TCK)") (class "Default")
      (node (ref "R2") (pin "1") (pinfunction "1_1") (pintype "passive"))
      (node (ref "U1") (pin "P110") (pinfunction "TCK_P110") (pintype "bidirectional"))
    )
    (net (code "101") (name "Net-(U1N-TDI)") (class "Default")
      (node (ref "R1") (pin "1") (pinfunction "1_1") (pintype "passive"))
      (node (ref "U1") (pin "P144") (pinfunction "TDI_P144") (pintype "bidirectional"))
    )
    (net (code "102") (name "Net-(U1N-TMS)") (class "Default")
      (node (ref "R3") (pin "1") (pinfunction "1_1") (pintype "passive"))
      (node (ref "U1") (pin "P111") (pinfunction "TMS_P111") (pintype "bidirectional"))
    )
    (net (code "103") (name "unconnected-(IC1-NC.1-Pad2)") (class "Default")
      (node (ref "IC1") (pin "2") (pinfunction "NC.1_2") (pintype "bidirectional"))
    )
    (net (code "104") (name "unconnected-(IC1-NC.2-Pad9)") (class "Default")
      (node (ref "IC1") (pin "9") (pinfunction "NC.2_9") (pintype "bidirectional"))
    )
    (net (code "105") (name "unconnected-(IC1-NC.3-Pad12)") (class "Default")
      (node (ref "IC1") (pin "12") (pinfunction "NC.3_12") (pintype "bidirectional"))
    )
    (net (code "106") (name "unconnected-(IC1-NC.4-Pad14)") (class "Default")
      (node (ref "IC1") (pin "14") (pinfunction "NC.4_14") (pintype "bidirectional"))
    )
    (net (code "107") (name "unconnected-(IC1-NC.5-Pad15)") (class "Default")
      (node (ref "IC1") (pin "15") (pinfunction "NC.5_15") (pintype "bidirectional"))
    )
    (net (code "108") (name "unconnected-(IC1-NC.6-Pad16)") (class "Default")
      (node (ref "IC1") (pin "16") (pinfunction "NC.6_16") (pintype "bidirectional"))
    )
    (net (code "109") (name "unconnected-(IC1-{slash}CEO-Pad13)") (class "Default")
      (node (ref "IC1") (pin "13") (pinfunction "/CEO_13") (pintype "bidirectional"))
    )
    (net (code "110") (name "unconnected-(U$2-TRI-PadENA)") (class "Default")
      (node (ref "U$2") (pin "ENA") (pinfunction "TRI_ENA") (pintype "input"))
    )
    (net (code "111") (name "unconnected-(U$3-VOUT2-Pad2)") (class "Default")
      (node (ref "U$3") (pin "2") (pinfunction "VOUT2_2") (pintype "bidirectional"))
    )
    (net (code "112") (name "unconnected-(U$4-VOUT2-Pad2)") (class "Default")
      (node (ref "U$4") (pin "2") (pinfunction "VOUT2_2") (pintype "bidirectional"))
    )
    (net (code "113") (name "unconnected-(U$5-PadP$1)") (class "Default")
      (node (ref "U$5") (pin "P$1") (pinfunction "P$1_P$1") (pintype "bidirectional"))
    )
    (net (code "114") (name "unconnected-(U$5-PadP$2)") (class "Default")
      (node (ref "U$5") (pin "P$2") (pinfunction "P$2_P$2") (pintype "bidirectional"))
    )
    (net (code "115") (name "unconnected-(U$5-PadP$3)") (class "Default")
      (node (ref "U$5") (pin "P$3") (pinfunction "P$3_P$3") (pintype "bidirectional"))
    )
    (net (code "116") (name "unconnected-(U$5-PadP$4)") (class "Default")
      (node (ref "U$5") (pin "P$4") (pinfunction "P$4_P$4") (pintype "bidirectional"))
    )
    (net (code "117") (name "unconnected-(U$5-PadP$5)") (class "Default")
      (node (ref "U$5") (pin "P$5") (pinfunction "P$5_P$5") (pintype "bidirectional"))
    )
    (net (code "118") (name "unconnected-(U$5-PadP$6)") (class "Default")
      (node (ref "U$5") (pin "P$6") (pinfunction "P$6_P$6") (pintype "bidirectional"))
    )
    (net (code "119") (name "unconnected-(U$5-PadP$7)") (class "Default")
      (node (ref "U$5") (pin "P$7") (pinfunction "P$7_P$7") (pintype "bidirectional"))
    )
    (net (code "120") (name "unconnected-(U$5-PadP$8)") (class "Default")
      (node (ref "U$5") (pin "P$8") (pinfunction "P$8_P$8") (pintype "bidirectional"))
    )
    (net (code "121") (name "unconnected-(U$5-PadP$9)") (class "Default")
      (node (ref "U$5") (pin "P$9") (pinfunction "P$9_P$9") (pintype "bidirectional"))
    )
    (net (code "122") (name "unconnected-(U$5-PadP$10)") (class "Default")
      (node (ref "U$5") (pin "P$10") (pinfunction "P$10_P$10") (pintype "bidirectional"))
    )
    (net (code "123") (name "unconnected-(U$5-PadP$11)") (class "Default")
      (node (ref "U$5") (pin "P$11") (pinfunction "P$11_P$11") (pintype "bidirectional"))
    )
    (net (code "124") (name "unconnected-(U$5-PadP$12)") (class "Default")
      (node (ref "U$5") (pin "P$12") (pinfunction "P$12_P$12") (pintype "bidirectional"))
    )
    (net (code "125") (name "unconnected-(U$5-PadP$13)") (class "Default")
      (node (ref "U$5") (pin "P$13") (pinfunction "P$13_P$13") (pintype "bidirectional"))
    )
    (net (code "126") (name "unconnected-(U$5-PadP$14)") (class "Default")
      (node (ref "U$5") (pin "P$14") (pinfunction "P$14_P$14") (pintype "bidirectional"))
    )
    (net (code "127") (name "unconnected-(U$5-PadP$15)") (class "Default")
      (node (ref "U$5") (pin "P$15") (pinfunction "P$15_P$15") (pintype "bidirectional"))
    )
    (net (code "128") (name "unconnected-(U$5-PadP$16)") (class "Default")
      (node (ref "U$5") (pin "P$16") (pinfunction "P$16_P$16") (pintype "bidirectional"))
    )
    (net (code "129") (name "unconnected-(U$5-PadP$17)") (class "Default")
      (node (ref "U$5") (pin "P$17") (pinfunction "P$17_P$17") (pintype "bidirectional"))
    )
    (net (code "130") (name "unconnected-(U$5-PadP$18)") (class "Default")
      (node (ref "U$5") (pin "P$18") (pinfunction "P$18_P$18") (pintype "bidirectional"))
    )
    (net (code "131") (name "unconnected-(U$5-PadP$19)") (class "Default")
      (node (ref "U$5") (pin "P$19") (pinfunction "P$19_P$19") (pintype "bidirectional"))
    )
    (net (code "132") (name "unconnected-(U$5-PadP$20)") (class "Default")
      (node (ref "U$5") (pin "P$20") (pinfunction "P$20_P$20") (pintype "bidirectional"))
    )
    (net (code "133") (name "unconnected-(U$5B-P$1-PadP$21)") (class "Default")
      (node (ref "U$5") (pin "P$21") (pinfunction "P$1_P$21") (pintype "bidirectional"))
    )
    (net (code "134") (name "unconnected-(U$5B-P$2-PadP$22)") (class "Default")
      (node (ref "U$5") (pin "P$22") (pinfunction "P$2_P$22") (pintype "bidirectional"))
    )
    (net (code "135") (name "unconnected-(U$5B-P$3-PadP$23)") (class "Default")
      (node (ref "U$5") (pin "P$23") (pinfunction "P$3_P$23") (pintype "bidirectional"))
    )
    (net (code "136") (name "unconnected-(U$5B-P$4-PadP$24)") (class "Default")
      (node (ref "U$5") (pin "P$24") (pinfunction "P$4_P$24") (pintype "bidirectional"))
    )
    (net (code "137") (name "unconnected-(U$5B-P$5-PadP$25)") (class "Default")
      (node (ref "U$5") (pin "P$25") (pinfunction "P$5_P$25") (pintype "bidirectional"))
    )
    (net (code "138") (name "unconnected-(U$5B-P$6-PadP$26)") (class "Default")
      (node (ref "U$5") (pin "P$26") (pinfunction "P$6_P$26") (pintype "bidirectional"))
    )
    (net (code "139") (name "unconnected-(U$5B-P$7-PadP$27)") (class "Default")
      (node (ref "U$5") (pin "P$27") (pinfunction "P$7_P$27") (pintype "bidirectional"))
    )
    (net (code "140") (name "unconnected-(U$5B-P$8-PadP$28)") (class "Default")
      (node (ref "U$5") (pin "P$28") (pinfunction "P$8_P$28") (pintype "bidirectional"))
    )
    (net (code "141") (name "unconnected-(U$5B-P$9-PadP$29)") (class "Default")
      (node (ref "U$5") (pin "P$29") (pinfunction "P$9_P$29") (pintype "bidirectional"))
    )
    (net (code "142") (name "unconnected-(U$5B-P$10-PadP$30)") (class "Default")
      (node (ref "U$5") (pin "P$30") (pinfunction "P$10_P$30") (pintype "bidirectional"))
    )
    (net (code "143") (name "unconnected-(U$5B-P$11-PadP$31)") (class "Default")
      (node (ref "U$5") (pin "P$31") (pinfunction "P$11_P$31") (pintype "bidirectional"))
    )
    (net (code "144") (name "unconnected-(U$5B-P$12-PadP$32)") (class "Default")
      (node (ref "U$5") (pin "P$32") (pinfunction "P$12_P$32") (pintype "bidirectional"))
    )
    (net (code "145") (name "unconnected-(U$5B-P$13-PadP$33)") (class "Default")
      (node (ref "U$5") (pin "P$33") (pinfunction "P$13_P$33") (pintype "bidirectional"))
    )
    (net (code "146") (name "unconnected-(U$5B-P$14-PadP$34)") (class "Default")
      (node (ref "U$5") (pin "P$34") (pinfunction "P$14_P$34") (pintype "bidirectional"))
    )
    (net (code "147") (name "unconnected-(U$5B-P$15-PadP$35)") (class "Default")
      (node (ref "U$5") (pin "P$35") (pinfunction "P$15_P$35") (pintype "bidirectional"))
    )
    (net (code "148") (name "unconnected-(U$5B-P$16-PadP$36)") (class "Default")
      (node (ref "U$5") (pin "P$36") (pinfunction "P$16_P$36") (pintype "bidirectional"))
    )
    (net (code "149") (name "unconnected-(U$5B-P$17-PadP$37)") (class "Default")
      (node (ref "U$5") (pin "P$37") (pinfunction "P$17_P$37") (pintype "bidirectional"))
    )
    (net (code "150") (name "unconnected-(U$5B-P$18-PadP$38)") (class "Default")
      (node (ref "U$5") (pin "P$38") (pinfunction "P$18_P$38") (pintype "bidirectional"))
    )
    (net (code "151") (name "unconnected-(U$5B-P$19-PadP$39)") (class "Default")
      (node (ref "U$5") (pin "P$39") (pinfunction "P$19_P$39") (pintype "bidirectional"))
    )
    (net (code "152") (name "unconnected-(U$5B-P$20-PadP$40)") (class "Default")
      (node (ref "U$5") (pin "P$40") (pinfunction "P$20_P$40") (pintype "bidirectional"))
    )
    (net (code "153") (name "unconnected-(U1A-IO_L01N_0VRP_0-PadP141)") (class "Default")
      (node (ref "U1") (pin "P141") (pinfunction "IO_L01N_0VRP_0_P141") (pintype "bidirectional"))
    )
    (net (code "154") (name "unconnected-(U1A-IO_L01P_0VRN_0-PadP140)") (class "Default")
      (node (ref "U1") (pin "P140") (pinfunction "IO_L01P_0VRN_0_P140") (pintype "bidirectional"))
    )
    (net (code "155") (name "unconnected-(U1A-IO_L27N_0-PadP137)") (class "Default")
      (node (ref "U1") (pin "P137") (pinfunction "IO_L27N_0_P137") (pintype "bidirectional"))
    )
    (net (code "156") (name "unconnected-(U1A-IO_L27P_0-PadP135)") (class "Default")
      (node (ref "U1") (pin "P135") (pinfunction "IO_L27P_0_P135") (pintype "bidirectional"))
    )
    (net (code "157") (name "unconnected-(U1A-IO_L30N_0-PadP132)") (class "Default")
      (node (ref "U1") (pin "P132") (pinfunction "IO_L30N_0_P132") (pintype "bidirectional"))
    )
    (net (code "158") (name "unconnected-(U1A-IO_L30P_0-PadP131)") (class "Default")
      (node (ref "U1") (pin "P131") (pinfunction "IO_L30P_0_P131") (pintype "bidirectional"))
    )
    (net (code "159") (name "unconnected-(U1A-IO_L31N_0-PadP130)") (class "Default")
      (node (ref "U1") (pin "P130") (pinfunction "IO_L31N_0_P130") (pintype "bidirectional"))
    )
    (net (code "160") (name "unconnected-(U1A-IO_L31P_0VREF_0-PadP129)") (class "Default")
      (node (ref "U1") (pin "P129") (pinfunction "IO_L31P_0VREF_0_P129") (pintype "bidirectional"))
    )
    (net (code "161") (name "unconnected-(U1A-IO_L32N_0GCLK7-PadP128)") (class "Default")
      (node (ref "U1") (pin "P128") (pinfunction "IO_L32N_0GCLK7_P128") (pintype "bidirectional"))
    )
    (net (code "162") (name "unconnected-(U1A-IO_L32P_0GCLK6-PadP127)") (class "Default")
      (node (ref "U1") (pin "P127") (pinfunction "IO_L32P_0GCLK6_P127") (pintype "bidirectional"))
    )
    (net (code "163") (name "unconnected-(U1C-IO-PadP116)") (class "Default")
      (node (ref "U1") (pin "P116") (pinfunction "IO_P116") (pintype "bidirectional"))
    )
    (net (code "164") (name "unconnected-(U1C-IO_L01N_1VRP_1-PadP113)") (class "Default")
      (node (ref "U1") (pin "P113") (pinfunction "IO_L01N_1VRP_1_P113") (pintype "bidirectional"))
    )
    (net (code "165") (name "unconnected-(U1C-IO_L01P_1VRN_1-PadP112)") (class "Default")
      (node (ref "U1") (pin "P112") (pinfunction "IO_L01P_1VRN_1_P112") (pintype "bidirectional"))
    )
    (net (code "166") (name "unconnected-(U1C-IO_L28N_1-PadP119)") (class "Default")
      (node (ref "U1") (pin "P119") (pinfunction "IO_L28N_1_P119") (pintype "bidirectional"))
    )
    (net (code "167") (name "unconnected-(U1C-IO_L28P_1-PadP118)") (class "Default")
      (node (ref "U1") (pin "P118") (pinfunction "IO_L28P_1_P118") (pintype "bidirectional"))
    )
    (net (code "168") (name "unconnected-(U1C-IO_L31N_1VREF_1-PadP123)") (class "Default")
      (node (ref "U1") (pin "P123") (pinfunction "IO_L31N_1VREF_1_P123") (pintype "bidirectional"))
    )
    (net (code "169") (name "unconnected-(U1C-IO_L31P_1-PadP122)") (class "Default")
      (node (ref "U1") (pin "P122") (pinfunction "IO_L31P_1_P122") (pintype "bidirectional"))
    )
    (net (code "170") (name "unconnected-(U1C-IO_L32N_1GCLK5-PadP125)") (class "Default")
      (node (ref "U1") (pin "P125") (pinfunction "IO_L32N_1GCLK5_P125") (pintype "bidirectional"))
    )
    (net (code "171") (name "unconnected-(U1C-IO_L32P_1GCLK4-PadP124)") (class "Default")
      (node (ref "U1") (pin "P124") (pinfunction "IO_L32P_1GCLK4_P124") (pintype "bidirectional"))
    )
    (net (code "172") (name "unconnected-(U1D-IO_L01N_2VRP_2-PadP108)") (class "Default")
      (node (ref "U1") (pin "P108") (pinfunction "IO_L01N_2VRP_2_P108") (pintype "bidirectional"))
    )
    (net (code "173") (name "unconnected-(U1D-IO_L01P_2VRN_2-PadP107)") (class "Default")
      (node (ref "U1") (pin "P107") (pinfunction "IO_L01P_2VRN_2_P107") (pintype "bidirectional"))
    )
    (net (code "174") (name "unconnected-(U1D-IO_L20N_2-PadP105)") (class "Default")
      (node (ref "U1") (pin "P105") (pinfunction "IO_L20N_2_P105") (pintype "bidirectional"))
    )
    (net (code "175") (name "unconnected-(U1D-IO_L20P_2-PadP104)") (class "Default")
      (node (ref "U1") (pin "P104") (pinfunction "IO_L20P_2_P104") (pintype "bidirectional"))
    )
    (net (code "176") (name "unconnected-(U1D-IO_L21N_2-PadP103)") (class "Default")
      (node (ref "U1") (pin "P103") (pinfunction "IO_L21N_2_P103") (pintype "bidirectional"))
    )
    (net (code "177") (name "unconnected-(U1D-IO_L21P_2-PadP102)") (class "Default")
      (node (ref "U1") (pin "P102") (pinfunction "IO_L21P_2_P102") (pintype "bidirectional"))
    )
    (net (code "178") (name "unconnected-(U1D-IO_L22N_2-PadP100)") (class "Default")
      (node (ref "U1") (pin "P100") (pinfunction "IO_L22N_2_P100") (pintype "bidirectional"))
    )
    (net (code "179") (name "unconnected-(U1D-IO_L22P_2-PadP99)") (class "Default")
      (node (ref "U1") (pin "P99") (pinfunction "IO_L22P_2_P99") (pintype "bidirectional"))
    )
    (net (code "180") (name "unconnected-(U1D-IO_L23N_2VREF_2-PadP98)") (class "Default")
      (node (ref "U1") (pin "P98") (pinfunction "IO_L23N_2VREF_2_P98") (pintype "bidirectional"))
    )
    (net (code "181") (name "unconnected-(U1D-IO_L23P_2-PadP97)") (class "Default")
      (node (ref "U1") (pin "P97") (pinfunction "IO_L23P_2_P97") (pintype "bidirectional"))
    )
    (net (code "182") (name "unconnected-(U1D-IO_L24N_2-PadP96)") (class "Default")
      (node (ref "U1") (pin "P96") (pinfunction "IO_L24N_2_P96") (pintype "bidirectional"))
    )
    (net (code "183") (name "unconnected-(U1D-IO_L24P_2-PadP95)") (class "Default")
      (node (ref "U1") (pin "P95") (pinfunction "IO_L24P_2_P95") (pintype "bidirectional"))
    )
    (net (code "184") (name "unconnected-(U1D-IO_L40N_2-PadP93)") (class "Default")
      (node (ref "U1") (pin "P93") (pinfunction "IO_L40N_2_P93") (pintype "bidirectional"))
    )
    (net (code "185") (name "unconnected-(U1D-IO_L40P_2VREF_2-PadP92)") (class "Default")
      (node (ref "U1") (pin "P92") (pinfunction "IO_L40P_2VREF_2_P92") (pintype "bidirectional"))
    )
    (net (code "186") (name "unconnected-(U1F-IO-PadP76)") (class "Default")
      (node (ref "U1") (pin "P76") (pinfunction "IO_P76") (pintype "bidirectional"))
    )
    (net (code "187") (name "unconnected-(U1F-IO_L01N_3VRP_3-PadP74)") (class "Default")
      (node (ref "U1") (pin "P74") (pinfunction "IO_L01N_3VRP_3_P74") (pintype "bidirectional"))
    )
    (net (code "188") (name "unconnected-(U1F-IO_L01P_3VRN_3-PadP73)") (class "Default")
      (node (ref "U1") (pin "P73") (pinfunction "IO_L01P_3VRN_3_P73") (pintype "bidirectional"))
    )
    (net (code "189") (name "unconnected-(U1F-IO_L20N_3-PadP78)") (class "Default")
      (node (ref "U1") (pin "P78") (pinfunction "IO_L20N_3_P78") (pintype "bidirectional"))
    )
    (net (code "190") (name "unconnected-(U1F-IO_L20P_3-PadP77)") (class "Default")
      (node (ref "U1") (pin "P77") (pinfunction "IO_L20P_3_P77") (pintype "bidirectional"))
    )
    (net (code "191") (name "unconnected-(U1F-IO_L21N_3-PadP80)") (class "Default")
      (node (ref "U1") (pin "P80") (pinfunction "IO_L21N_3_P80") (pintype "bidirectional"))
    )
    (net (code "192") (name "unconnected-(U1F-IO_L21P_3-PadP79)") (class "Default")
      (node (ref "U1") (pin "P79") (pinfunction "IO_L21P_3_P79") (pintype "bidirectional"))
    )
    (net (code "193") (name "unconnected-(U1F-IO_L22N_3-PadP83)") (class "Default")
      (node (ref "U1") (pin "P83") (pinfunction "IO_L22N_3_P83") (pintype "bidirectional"))
    )
    (net (code "194") (name "unconnected-(U1F-IO_L22P_3-PadP82)") (class "Default")
      (node (ref "U1") (pin "P82") (pinfunction "IO_L22P_3_P82") (pintype "bidirectional"))
    )
    (net (code "195") (name "unconnected-(U1F-IO_L23N_3-PadP85)") (class "Default")
      (node (ref "U1") (pin "P85") (pinfunction "IO_L23N_3_P85") (pintype "bidirectional"))
    )
    (net (code "196") (name "unconnected-(U1F-IO_L23P_3VREF_3-PadP84)") (class "Default")
      (node (ref "U1") (pin "P84") (pinfunction "IO_L23P_3VREF_3_P84") (pintype "bidirectional"))
    )
    (net (code "197") (name "unconnected-(U1F-IO_L24N_3-PadP87)") (class "Default")
      (node (ref "U1") (pin "P87") (pinfunction "IO_L24N_3_P87") (pintype "bidirectional"))
    )
    (net (code "198") (name "unconnected-(U1F-IO_L24P_3-PadP86)") (class "Default")
      (node (ref "U1") (pin "P86") (pinfunction "IO_L24P_3_P86") (pintype "bidirectional"))
    )
    (net (code "199") (name "unconnected-(U1F-IO_L40N_3VREF_3-PadP90)") (class "Default")
      (node (ref "U1") (pin "P90") (pinfunction "IO_L40N_3VREF_3_P90") (pintype "bidirectional"))
    )
    (net (code "200") (name "unconnected-(U1F-IO_L40P_3-PadP89)") (class "Default")
      (node (ref "U1") (pin "P89") (pinfunction "IO_L40P_3_P89") (pintype "bidirectional"))
    )
    (net (code "201") (name "unconnected-(U1G-IOVREF_4-PadP70)") (class "Default")
      (node (ref "U1") (pin "P70") (pinfunction "IOVREF_4_P70") (pintype "bidirectional"))
    )
    (net (code "202") (name "unconnected-(U1G-IO_L01N_4VRP_4-PadP69)") (class "Default")
      (node (ref "U1") (pin "P69") (pinfunction "IO_L01N_4VRP_4_P69") (pintype "bidirectional"))
    )
    (net (code "203") (name "unconnected-(U1G-IO_L01P_4VRN_4-PadP68)") (class "Default")
      (node (ref "U1") (pin "P68") (pinfunction "IO_L01P_4VRN_4_P68") (pintype "bidirectional"))
    )
    (net (code "204") (name "unconnected-(U1G-IO_L27P_4D1-PadP63)") (class "Default")
      (node (ref "U1") (pin "P63") (pinfunction "IO_L27P_4D1_P63") (pintype "bidirectional"))
    )
    (net (code "205") (name "unconnected-(U1G-IO_L30N_4D2-PadP60)") (class "Default")
      (node (ref "U1") (pin "P60") (pinfunction "IO_L30N_4D2_P60") (pintype "bidirectional"))
    )
    (net (code "206") (name "unconnected-(U1G-IO_L30P_4D3-PadP59)") (class "Default")
      (node (ref "U1") (pin "P59") (pinfunction "IO_L30P_4D3_P59") (pintype "bidirectional"))
    )
    (net (code "207") (name "unconnected-(U1G-IO_L31P_4DOUTBUSY-PadP57)") (class "Default")
      (node (ref "U1") (pin "P57") (pinfunction "IO_L31P_4DOUTBUSY_P57") (pintype "bidirectional"))
    )
    (net (code "208") (name "unconnected-(U1G-IO_L32N_4GCLK1-PadP56)") (class "Default")
      (node (ref "U1") (pin "P56") (pinfunction "IO_L32N_4GCLK1_P56") (pintype "bidirectional"))
    )
    (net (code "209") (name "unconnected-(U1I-IOVREF_5-PadP44)") (class "Default")
      (node (ref "U1") (pin "P44") (pinfunction "IOVREF_5_P44") (pintype "bidirectional"))
    )
    (net (code "210") (name "unconnected-(U1I-IO_L01N_5RDWR_B-PadP41)") (class "Default")
      (node (ref "U1") (pin "P41") (pinfunction "IO_L01N_5RDWR_B_P41") (pintype "bidirectional"))
    )
    (net (code "211") (name "unconnected-(U1I-IO_L01P_5CS_B-PadP40)") (class "Default")
      (node (ref "U1") (pin "P40") (pinfunction "IO_L01P_5CS_B_P40") (pintype "bidirectional"))
    )
    (net (code "212") (name "unconnected-(U1I-IO_L28N_5D6-PadP47)") (class "Default")
      (node (ref "U1") (pin "P47") (pinfunction "IO_L28N_5D6_P47") (pintype "bidirectional"))
    )
    (net (code "213") (name "unconnected-(U1I-IO_L28P_5D7-PadP46)") (class "Default")
      (node (ref "U1") (pin "P46") (pinfunction "IO_L28P_5D7_P46") (pintype "bidirectional"))
    )
    (net (code "214") (name "unconnected-(U1I-IO_L31N_5D4-PadP51)") (class "Default")
      (node (ref "U1") (pin "P51") (pinfunction "IO_L31N_5D4_P51") (pintype "bidirectional"))
    )
    (net (code "215") (name "unconnected-(U1I-IO_L31P_5D5-PadP50)") (class "Default")
      (node (ref "U1") (pin "P50") (pinfunction "IO_L31P_5D5_P50") (pintype "bidirectional"))
    )
    (net (code "216") (name "unconnected-(U1I-IO_L32N_5GCLK3-PadP53)") (class "Default")
      (node (ref "U1") (pin "P53") (pinfunction "IO_L32N_5GCLK3_P53") (pintype "bidirectional"))
    )
    (net (code "217") (name "unconnected-(U1I-IO_L32P_5GCLK2-PadP52)") (class "Default")
      (node (ref "U1") (pin "P52") (pinfunction "IO_L32P_5GCLK2_P52") (pintype "bidirectional"))
    )
    (net (code "218") (name "unconnected-(U1N-HSWAP_EN-PadP142)") (class "Default")
      (node (ref "U1") (pin "P142") (pinfunction "HSWAP_EN_P142") (pintype "bidirectional"))
    )
    (net (code "219") (name "unconnected-(X1-3-Pad2)") (class "Default")
      (node (ref "X1") (pin "2") (pinfunction "3_2") (pintype "passive"))
    )
    (net (code "220") (name "unconnected-(X2-Pad10)") (class "Default")
      (node (ref "X2") (pin "10") (pinfunction "10_10") (pintype "passive"))
    )
    (net (code "221") (name "unconnected-(X2-Pad12)") (class "Default")
      (node (ref "X2") (pin "12") (pinfunction "12_12") (pintype "passive"))
    )
    (net (code "222") (name "unconnected-(X3-Pad2)") (class "Default")
      (node (ref "X3") (pin "2") (pinfunction "2_2") (pintype "passive"))
    )
    (net (code "223") (name "unconnected-(X3-Pad8)") (class "Default")
      (node (ref "X3") (pin "8") (pinfunction "8_8") (pintype "passive"))
    )
  )
)
